# ESP01.net
KiCad netlist of a schematic drawn in EAGLE
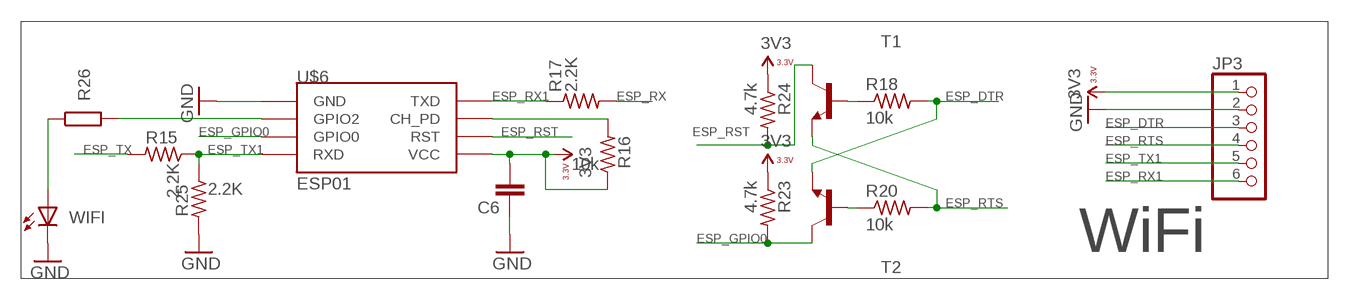
[diagram p0: schematic, sheet 1]

(export (version "E")
  (design (tool "Eeschema 10.0.6"))
  (components
    (comp (ref "C6")
      (value "C-EU050-024X044")
      (footprint "eagle-import:C050-024X044")
      (libsource (lib "eagle-import") (part "C-EU050-024X044"))
    )
    (comp (ref "JP3")
      (value "PINHD-1X6")
      (footprint "eagle-import:1X06")
      (libsource (lib "eagle-import") (part "PINHD-1X6"))
    )
    (comp (ref "R15")
      (value "2.2K")
      (footprint "eagle-import:0204_7")
      (libsource (lib "eagle-import") (part "R-US_0204/7"))
    )
    (comp (ref "R16")
      (value "10k")
      (footprint "eagle-import:0204_7")
      (libsource (lib "eagle-import") (part "R-US_0204/7"))
    )
    (comp (ref "R17")
      (value "2.2K")
      (footprint "eagle-import:0204_7")
      (libsource (lib "eagle-import") (part "R-US_0204/7"))
    )
    (comp (ref "R18")
      (value "10k")
      (footprint "eagle-import:0204_7")
      (libsource (lib "eagle-import") (part "R-US_0204/7"))
    )
    (comp (ref "R20")
      (value "10k")
      (footprint "eagle-import:0204_7")
      (libsource (lib "eagle-import") (part "R-US_0204/7"))
    )
    (comp (ref "R23")
      (value "4.7k")
      (footprint "eagle-import:0204_7")
      (libsource (lib "eagle-import") (part "R-US_0204/7"))
    )
    (comp (ref "R24")
      (value "4.7k")
      (footprint "eagle-import:0204_7")
      (libsource (lib "eagle-import") (part "R-US_0204/7"))
    )
    (comp (ref "R25")
      (value "2.2K")
      (footprint "eagle-import:0204_7")
      (libsource (lib "eagle-import") (part "R-US_0204/7"))
    )
    (comp (ref "R26")
      (value "R-EU_0204/7")
      (footprint "eagle-import:0204_7")
      (libsource (lib "eagle-import") (part "R-EU_0204/7"))
    )
    (comp (ref "T1")
      (value "BC547-NPN-TO92-CBE")
      (footprint "eagle-import:TO92-CBE")
      (libsource (lib "eagle-import") (part "-NPN-TO92-CBEBC547"))
    )
    (comp (ref "T2")
      (value "BC547-NPN-TO92-CBE")
      (footprint "eagle-import:TO92-CBE")
      (libsource (lib "eagle-import") (part "-NPN-TO92-CBEBC547"))
    )
    (comp (ref "U$6")
      (value "ESP01")
      (footprint "eagle-import:ESP01")
      (libsource (lib "eagle-import") (part "ESP01"))
    )
    (comp (ref "WIFI")
      (value "LED3MM")
      (footprint "eagle-import:LED3MM")
      (libsource (lib "eagle-import") (part "LED3MM"))
    )
  )
  (nets
    (net (code "1") (name "/ESP_DTR") (class "Default")
      (node (ref "JP3") (pin "3") (pinfunction "3_3") (pintype "passive"))
      (node (ref "R18") (pin "2") (pinfunction "2_2") (pintype "passive"))
      (node (ref "T2") (pin "E") (pinfunction "E_E") (pintype "passive"))
    )
    (net (code "2") (name "/ESP_GPIO0") (class "Default")
      (node (ref "R23") (pin "2") (pinfunction "2_2") (pintype "passive"))
      (node (ref "T2") (pin "C") (pinfunction "C_C") (pintype "passive"))
      (node (ref "U$6") (pin "GPIO0") (pinfunction "GPIO0_GPIO0") (pintype "bidirectional"))
    )
    (net (code "3") (name "/ESP_RST") (class "Default")
      (node (ref "R24") (pin "2") (pinfunction "2_2") (pintype "passive"))
      (node (ref "T1") (pin "C") (pinfunction "C_C") (pintype "passive"))
      (node (ref "U$6") (pin "RST") (pinfunction "RST_RST") (pintype "bidirectional"))
    )
    (net (code "4") (name "/ESP_RTS") (class "Default")
      (node (ref "JP3") (pin "4") (pinfunction "4_4") (pintype "passive"))
      (node (ref "R20") (pin "2") (pinfunction "2_2") (pintype "passive"))
      (node (ref "T1") (pin "E") (pinfunction "E_E") (pintype "passive"))
    )
    (net (code "5") (name "/ESP_RX") (class "Default")
      (node (ref "R17") (pin "2") (pinfunction "2_2") (pintype "passive"))
    )
    (net (code "6") (name "/ESP_RX1") (class "Default")
      (node (ref "JP3") (pin "6") (pinfunction "6_6") (pintype "passive"))
      (node (ref "R17") (pin "1") (pinfunction "1_1") (pintype "passive"))
      (node (ref "U$6") (pin "TX") (pinfunction "TXD_TX") (pintype "bidirectional"))
    )
    (net (code "7") (name "/ESP_TX") (class "Default")
      (node (ref "R15") (pin "2") (pinfunction "2_2") (pintype "passive"))
    )
    (net (code "8") (name "/ESP_TX1") (class "Default")
      (node (ref "JP3") (pin "5") (pinfunction "5_5") (pintype "passive"))
      (node (ref "R15") (pin "1") (pinfunction "1_1") (pintype "passive"))
      (node (ref "R25") (pin "1") (pinfunction "1_1") (pintype "passive"))
      (node (ref "U$6") (pin "RX") (pinfunction "RXD_RX") (pintype "bidirectional"))
    )
    (net (code "9") (name "3V3") (class "Default")
      (node (ref "C6") (pin "2") (pinfunction "2_2") (pintype "passive"))
      (node (ref "JP3") (pin "1") (pinfunction "1_1") (pintype "passive"))
      (node (ref "R16") (pin "1") (pinfunction "1_1") (pintype "passive"))
      (node (ref "R23") (pin "1") (pinfunction "1_1") (pintype "passive"))
      (node (ref "R24") (pin "1") (pinfunction "1_1") (pintype "passive"))
      (node (ref "U$6") (pin "VCC") (pinfunction "VCC_VCC") (pintype "bidirectional"))
    )
    (net (code "10") (name "GND") (class "Default")
      (node (ref "C6") (pin "1") (pinfunction "1_1") (pintype "passive"))
      (node (ref "JP3") (pin "2") (pinfunction "2_2") (pintype "passive"))
      (node (ref "R25") (pin "2") (pinfunction "2_2") (pintype "passive"))
      (node (ref "U$6") (pin "GND") (pinfunction "GND_GND") (pintype "bidirectional"))
      (node (ref "WIFI") (pin "K") (pinfunction "C_K") (pintype "passive"))
    )
    (net (code "11") (name "Net-(R16-Pad2)") (class "Default")
      (node (ref "R16") (pin "2") (pinfunction "2_2") (pintype "passive"))
      (node (ref "U$6") (pin "CH_PD") (pinfunction "CH_PD_CH_PD") (pintype "bidirectional"))
    )
    (net (code "12") (name "Net-(R18-Pad1)") (class "Default")
      (node (ref "R18") (pin "1") (pinfunction "1_1") (pintype "passive"))
      (node (ref "T1") (pin "B") (pinfunction "B_B") (pintype "passive"))
    )
    (net (code "13") (name "Net-(R20-Pad1)") (class "Default")
      (node (ref "R20") (pin "1") (pinfunction "1_1") (pintype "passive"))
      (node (ref "T2") (pin "B") (pinfunction "B_B") (pintype "passive"))
    )
    (net (code "14") (name "Net-(R26-Pad1)") (class "Default")
      (node (ref "R26") (pin "1") (pinfunction "1_1") (pintype "passive"))
      (node (ref "WIFI") (pin "A") (pinfunction "A_A") (pintype "passive"))
    )
    (net (code "15") (name "Net-(R26-Pad2)") (class "Default")
      (node (ref "R26") (pin "2") (pinfunction "2_2") (pintype "passive"))
      (node (ref "U$6") (pin "GPIO2") (pinfunction "GPIO2_GPIO2") (pintype "bidirectional"))
    )
  )
)
